# IMX_Analog_Interface_Circuit.net
KiCad netlist of a schematic drawn in Altium Designer
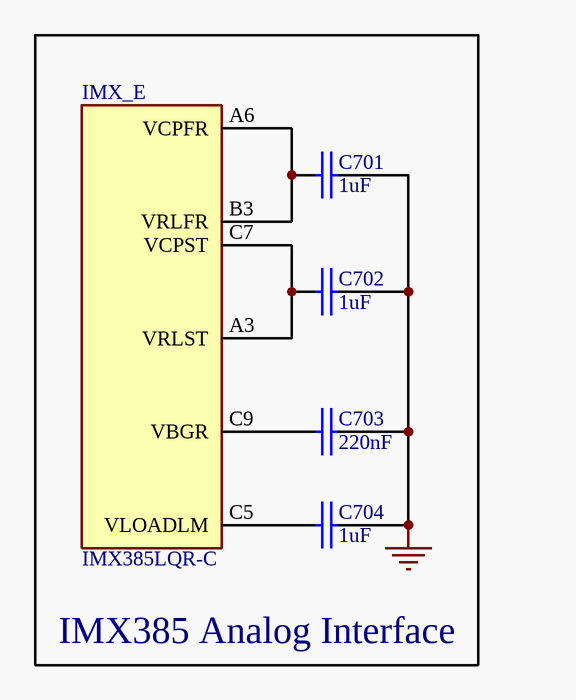
[diagram p0: IMX_Analog Interface Circuit.SchDoc]

(export (version "E")
  (design (tool "Eeschema 10.0.6"))
  (components
    (comp (ref "C701")
      (value "1uF")
      (footprint "Capacitor, 0402")
      (description "Ceramic Capacitor, 10V, 10% +/- Tol, X7R, 1uF, SMD, 0402, #GRM155Z71A105KE01D, JLC#C528974")
      (libsource (lib "Component Library") (part "Capacitor, 0402, 1uF"))
    )
    (comp (ref "C702")
      (value "1uF")
      (footprint "Capacitor, 0402")
      (description "Ceramic Capacitor, 10V, 10% +/- Tol, X7R, 1uF, SMD, 0402, #GRM155Z71A105KE01D, JLC#C528974")
      (libsource (lib "Component Library") (part "Capacitor, 0402, 1uF"))
    )
    (comp (ref "C703")
      (value "220nF")
      (footprint "Capacitor, 0402")
      (description "Ceramic Capacitor, 16V, 10% +/- Tol, X7R, 220nF, SMD, 0402, #CL05B224KO5NNNC, JLC#C16772")
      (libsource (lib "Component Library") (part "Capacitor, 0402, 220nF"))
    )
    (comp (ref "C704")
      (value "1uF")
      (footprint "Capacitor, 0402")
      (description "Ceramic Capacitor, 10V, 10% +/- Tol, X7R, 1uF, SMD, 0402, #GRM155Z71A105KE01D, JLC#C528974")
      (libsource (lib "Component Library") (part "Capacitor, 0402, 1uF"))
    )
    (comp (ref "IMX_")
      (value "IMX385LQR-C")
      (footprint "IMX385LQR")
      (libsource (lib "Component Library") (part "IMX385LQR"))
    )
  )
  (nets
    (net (code "1") (name "GND") (class "Default")
      (node (ref "C701") (pin "1") (pinfunction "1_1") (pintype "passive"))
      (node (ref "C702") (pin "1") (pinfunction "1_1") (pintype "passive"))
      (node (ref "C703") (pin "1") (pinfunction "1_1") (pintype "passive"))
      (node (ref "C704") (pin "2") (pinfunction "2_2") (pintype "passive"))
    )
    (net (code "2") (name "Net-(IMX_E-VBGR)") (class "Default")
      (node (ref "C703") (pin "2") (pinfunction "2_2") (pintype "passive"))
      (node (ref "IMX_") (pin "C9") (pinfunction "VBGR_C9") (pintype "passive"))
    )
    (net (code "3") (name "Net-(IMX_E-VCPFR)") (class "Default")
      (node (ref "C701") (pin "2") (pinfunction "2_2") (pintype "passive"))
      (node (ref "IMX_") (pin "A6") (pinfunction "VCPFR_A6") (pintype "passive"))
      (node (ref "IMX_") (pin "B3") (pinfunction "VRLFR_B3") (pintype "passive"))
    )
    (net (code "4") (name "Net-(IMX_E-VCPST)") (class "Default")
      (node (ref "C702") (pin "2") (pinfunction "2_2") (pintype "passive"))
      (node (ref "IMX_") (pin "A3") (pinfunction "VRLST_A3") (pintype "passive"))
      (node (ref "IMX_") (pin "C7") (pinfunction "VCPST_C7") (pintype "passive"))
    )
    (net (code "5") (name "Net-(IMX_E-VLOADLM)") (class "Default")
      (node (ref "C704") (pin "1") (pinfunction "1_1") (pintype "passive"))
      (node (ref "IMX_") (pin "C5") (pinfunction "VLOADLM_C5") (pintype "passive"))
    )
  )
)
